# espbreakout12e-1206.net
KiCad netlist of a schematic drawn in EAGLE
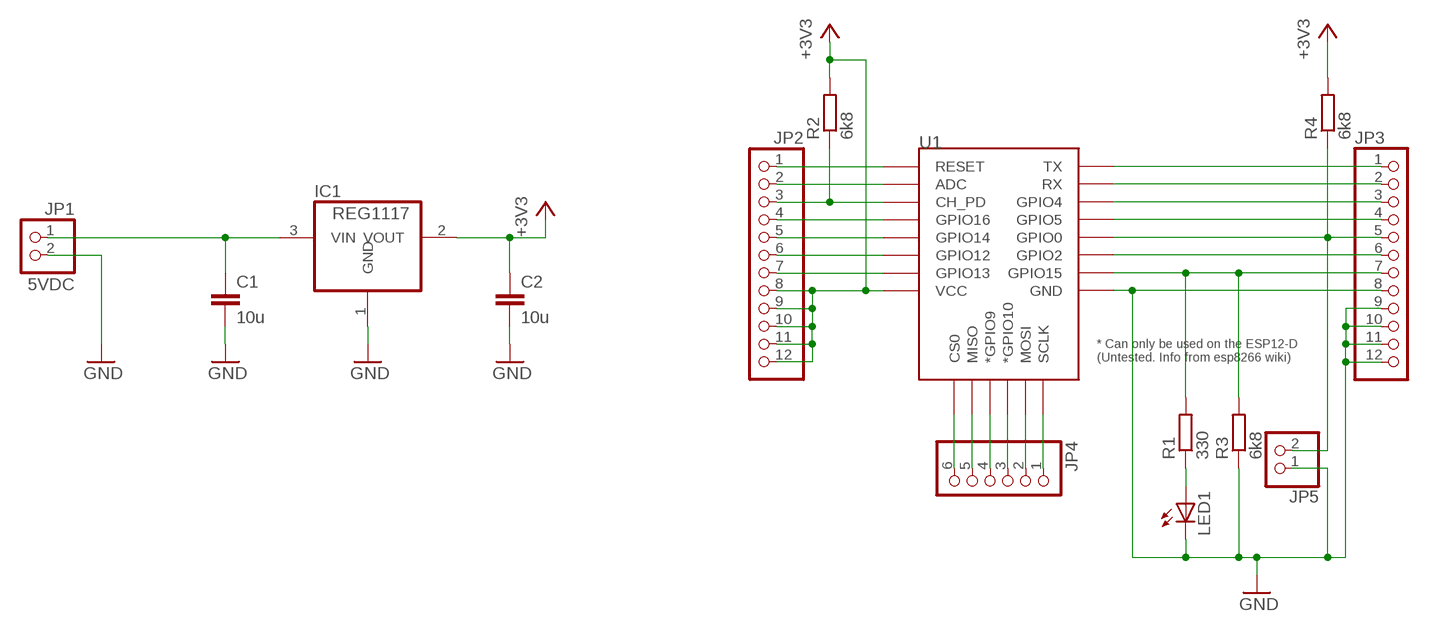
[diagram p0: schematic, sheet 1]

(export (version "E")
  (design (tool "Eeschema 10.0.6"))
  (components
    (comp (ref "C1")
      (value "10u")
      (footprint "eagle-import:C1206K")
      (libsource (lib "eagle-import") (part "C-EUC1206K"))
    )
    (comp (ref "C2")
      (value "10u")
      (footprint "eagle-import:C1206K")
      (libsource (lib "eagle-import") (part "C-EUC1206K"))
    )
    (comp (ref "IC1")
      (value "REG1117")
      (footprint "eagle-import:SOT223")
      (libsource (lib "eagle-import") (part "REG1117"))
    )
    (comp (ref "JP1")
      (value "5VDC")
      (footprint "eagle-import:1X02")
      (libsource (lib "eagle-import") (part "PINHD-1X2"))
    )
    (comp (ref "JP2")
      (value "PINHD-1X12")
      (footprint "eagle-import:1X12")
      (libsource (lib "eagle-import") (part "PINHD-1X12"))
    )
    (comp (ref "JP3")
      (value "PINHD-1X12")
      (footprint "eagle-import:1X12")
      (libsource (lib "eagle-import") (part "PINHD-1X12"))
    )
    (comp (ref "JP4")
      (value "PINHD-1X6")
      (footprint "eagle-import:1X06")
      (libsource (lib "eagle-import") (part "PINHD-1X6"))
    )
    (comp (ref "JP5")
      (value "PINHD-1X2")
      (footprint "eagle-import:1X02")
      (libsource (lib "eagle-import") (part "PINHD-1X2"))
    )
    (comp (ref "LED1")
      (value "LEDSML1206")
      (footprint "eagle-import:SML1206")
      (libsource (lib "eagle-import") (part "LEDSML1206"))
    )
    (comp (ref "R1")
      (value "330")
      (footprint "eagle-import:R1206")
      (libsource (lib "eagle-import") (part "R-EU_R1206"))
    )
    (comp (ref "R2")
      (value "6k8")
      (footprint "eagle-import:R1206")
      (libsource (lib "eagle-import") (part "R-EU_R1206"))
    )
    (comp (ref "R3")
      (value "6k8")
      (footprint "eagle-import:R1206")
      (libsource (lib "eagle-import") (part "R-EU_R1206"))
    )
    (comp (ref "R4")
      (value "6k8")
      (footprint "eagle-import:R1206")
      (libsource (lib "eagle-import") (part "R-EU_R1206"))
    )
    (comp (ref "U1")
      (value "ESP12ESMD")
      (footprint "eagle-import:ESP12E-SMD")
      (libsource (lib "eagle-import") (part "ESP12ESMD"))
    )
  )
  (nets
    (net (code "1") (name "+3V3") (class "Default")
      (node (ref "C2") (pin "1") (pinfunction "1_1") (pintype "passive"))
      (node (ref "IC1") (pin "2") (pinfunction "VOUT_2") (pintype "output"))
      (node (ref "JP2") (pin "10") (pinfunction "10_10") (pintype "passive"))
      (node (ref "JP2") (pin "11") (pinfunction "11_11") (pintype "passive"))
      (node (ref "JP2") (pin "12") (pinfunction "12_12") (pintype "passive"))
      (node (ref "JP2") (pin "8") (pinfunction "8_8") (pintype "passive"))
      (node (ref "JP2") (pin "9") (pinfunction "9_9") (pintype "passive"))
      (node (ref "R2") (pin "2") (pinfunction "2_2") (pintype "passive"))
      (node (ref "R4") (pin "2") (pinfunction "2_2") (pintype "passive"))
      (node (ref "U1") (pin "VCC") (pinfunction "VCC_VCC") (pintype "bidirectional"))
    )
    (net (code "2") (name "GND") (class "Default")
      (node (ref "C1") (pin "2") (pinfunction "2_2") (pintype "passive"))
      (node (ref "C2") (pin "2") (pinfunction "2_2") (pintype "passive"))
      (node (ref "IC1") (pin "1") (pinfunction "GND_1") (pintype "power_in"))
      (node (ref "JP1") (pin "2") (pinfunction "2_2") (pintype "passive"))
      (node (ref "JP3") (pin "10") (pinfunction "10_10") (pintype "passive"))
      (node (ref "JP3") (pin "11") (pinfunction "11_11") (pintype "passive"))
      (node (ref "JP3") (pin "12") (pinfunction "12_12") (pintype "passive"))
      (node (ref "JP3") (pin "8") (pinfunction "8_8") (pintype "passive"))
      (node (ref "JP3") (pin "9") (pinfunction "9_9") (pintype "passive"))
      (node (ref "JP5") (pin "1") (pinfunction "1_1") (pintype "passive"))
      (node (ref "LED1") (pin "C") (pinfunction "C_C") (pintype "passive"))
      (node (ref "R3") (pin "1") (pinfunction "1_1") (pintype "passive"))
      (node (ref "U1") (pin "GND") (pinfunction "GND_GND") (pintype "bidirectional"))
    )
    (net (code "3") (name "Net-(IC1-VIN)") (class "Default")
      (node (ref "C1") (pin "1") (pinfunction "1_1") (pintype "passive"))
      (node (ref "IC1") (pin "3") (pinfunction "VIN_3") (pintype "input"))
      (node (ref "JP1") (pin "1") (pinfunction "1_1") (pintype "passive"))
    )
    (net (code "4") (name "Net-(JP2-Pad1)") (class "Default")
      (node (ref "JP2") (pin "1") (pinfunction "1_1") (pintype "passive"))
      (node (ref "U1") (pin "RESET") (pinfunction "RESET_RESET") (pintype "bidirectional"))
    )
    (net (code "5") (name "Net-(JP2-Pad2)") (class "Default")
      (node (ref "JP2") (pin "2") (pinfunction "2_2") (pintype "passive"))
      (node (ref "U1") (pin "ADC") (pinfunction "ADC_ADC") (pintype "bidirectional"))
    )
    (net (code "6") (name "Net-(JP2-Pad3)") (class "Default")
      (node (ref "JP2") (pin "3") (pinfunction "3_3") (pintype "passive"))
      (node (ref "R2") (pin "1") (pinfunction "1_1") (pintype "passive"))
      (node (ref "U1") (pin "CH_PD") (pinfunction "CH_PD_CH_PD") (pintype "bidirectional"))
    )
    (net (code "7") (name "Net-(JP2-Pad4)") (class "Default")
      (node (ref "JP2") (pin "4") (pinfunction "4_4") (pintype "passive"))
      (node (ref "U1") (pin "GPIO16") (pinfunction "GPIO16_GPIO16") (pintype "bidirectional"))
    )
    (net (code "8") (name "Net-(JP2-Pad5)") (class "Default")
      (node (ref "JP2") (pin "5") (pinfunction "5_5") (pintype "passive"))
      (node (ref "U1") (pin "GPIO14") (pinfunction "GPIO14_GPIO14") (pintype "bidirectional"))
    )
    (net (code "9") (name "Net-(JP2-Pad6)") (class "Default")
      (node (ref "JP2") (pin "6") (pinfunction "6_6") (pintype "passive"))
      (node (ref "U1") (pin "GPIO12") (pinfunction "GPIO12_GPIO12") (pintype "bidirectional"))
    )
    (net (code "10") (name "Net-(JP2-Pad7)") (class "Default")
      (node (ref "JP2") (pin "7") (pinfunction "7_7") (pintype "passive"))
      (node (ref "U1") (pin "GPIO13") (pinfunction "GPIO13_GPIO13") (pintype "bidirectional"))
    )
    (net (code "11") (name "Net-(JP3-Pad3)") (class "Default")
      (node (ref "JP3") (pin "3") (pinfunction "3_3") (pintype "passive"))
      (node (ref "U1") (pin "GPIO4") (pinfunction "GPIO4_GPIO4") (pintype "bidirectional"))
    )
    (net (code "12") (name "Net-(JP3-Pad4)") (class "Default")
      (node (ref "JP3") (pin "4") (pinfunction "4_4") (pintype "passive"))
      (node (ref "U1") (pin "GPIO5") (pinfunction "GPIO5_GPIO5") (pintype "bidirectional"))
    )
    (net (code "13") (name "Net-(JP3-Pad5)") (class "Default")
      (node (ref "JP3") (pin "5") (pinfunction "5_5") (pintype "passive"))
      (node (ref "JP5") (pin "2") (pinfunction "2_2") (pintype "passive"))
      (node (ref "R4") (pin "1") (pinfunction "1_1") (pintype "passive"))
      (node (ref "U1") (pin "GPIO0") (pinfunction "GPIO0_GPIO0") (pintype "bidirectional"))
    )
    (net (code "14") (name "Net-(JP3-Pad6)") (class "Default")
      (node (ref "JP3") (pin "6") (pinfunction "6_6") (pintype "passive"))
      (node (ref "U1") (pin "GPIO2") (pinfunction "GPIO2_GPIO2") (pintype "bidirectional"))
    )
    (net (code "15") (name "Net-(JP3-Pad7)") (class "Default")
      (node (ref "JP3") (pin "7") (pinfunction "7_7") (pintype "passive"))
      (node (ref "R1") (pin "2") (pinfunction "2_2") (pintype "passive"))
      (node (ref "R3") (pin "2") (pinfunction "2_2") (pintype "passive"))
      (node (ref "U1") (pin "GPIO15") (pinfunction "GPIO15_GPIO15") (pintype "bidirectional"))
    )
    (net (code "16") (name "Net-(JP4-Pad1)") (class "Default")
      (node (ref "JP4") (pin "1") (pinfunction "1_1") (pintype "passive"))
      (node (ref "U1") (pin "SCLK") (pinfunction "SCLK_SCLK") (pintype "bidirectional"))
    )
    (net (code "17") (name "Net-(JP4-Pad2)") (class "Default")
      (node (ref "JP4") (pin "2") (pinfunction "2_2") (pintype "passive"))
      (node (ref "U1") (pin "MOSI") (pinfunction "MOSI_MOSI") (pintype "bidirectional"))
    )
    (net (code "18") (name "Net-(JP4-Pad5)") (class "Default")
      (node (ref "JP4") (pin "5") (pinfunction "5_5") (pintype "passive"))
      (node (ref "U1") (pin "MISO") (pinfunction "MISO_MISO") (pintype "bidirectional"))
    )
    (net (code "19") (name "Net-(JP4-Pad6)") (class "Default")
      (node (ref "JP4") (pin "6") (pinfunction "6_6") (pintype "passive"))
      (node (ref "U1") (pin "CS0") (pinfunction "CS0_CS0") (pintype "bidirectional"))
    )
    (net (code "20") (name "Net-(LED1-PadA)") (class "Default")
      (node (ref "LED1") (pin "A") (pinfunction "A_A") (pintype "passive"))
      (node (ref "R1") (pin "1") (pinfunction "1_1") (pintype "passive"))
    )
    (net (code "21") (name "Net-(U1-*GPIO9)") (class "Default")
      (node (ref "JP4") (pin "4") (pinfunction "4_4") (pintype "passive"))
      (node (ref "U1") (pin "GPIO9") (pinfunction "*GPIO9_GPIO9") (pintype "bidirectional"))
    )
    (net (code "22") (name "Net-(U1-*GPIO10)") (class "Default")
      (node (ref "JP4") (pin "3") (pinfunction "3_3") (pintype "passive"))
      (node (ref "U1") (pin "GPIO10") (pinfunction "*GPIO10_GPIO10") (pintype "bidirectional"))
    )
    (net (code "23") (name "Net-(U1-RX)") (class "Default")
      (node (ref "JP3") (pin "2") (pinfunction "2_2") (pintype "passive"))
      (node (ref "U1") (pin "RXD0") (pinfunction "RX_RXD0") (pintype "bidirectional"))
    )
    (net (code "24") (name "Net-(U1-TX)") (class "Default")
      (node (ref "JP3") (pin "1") (pinfunction "1_1") (pintype "passive"))
      (node (ref "U1") (pin "TXD0") (pinfunction "TX_TXD0") (pintype "bidirectional"))
    )
  )
)
